# Power.net
KiCad netlist of a schematic drawn in Altium Designer
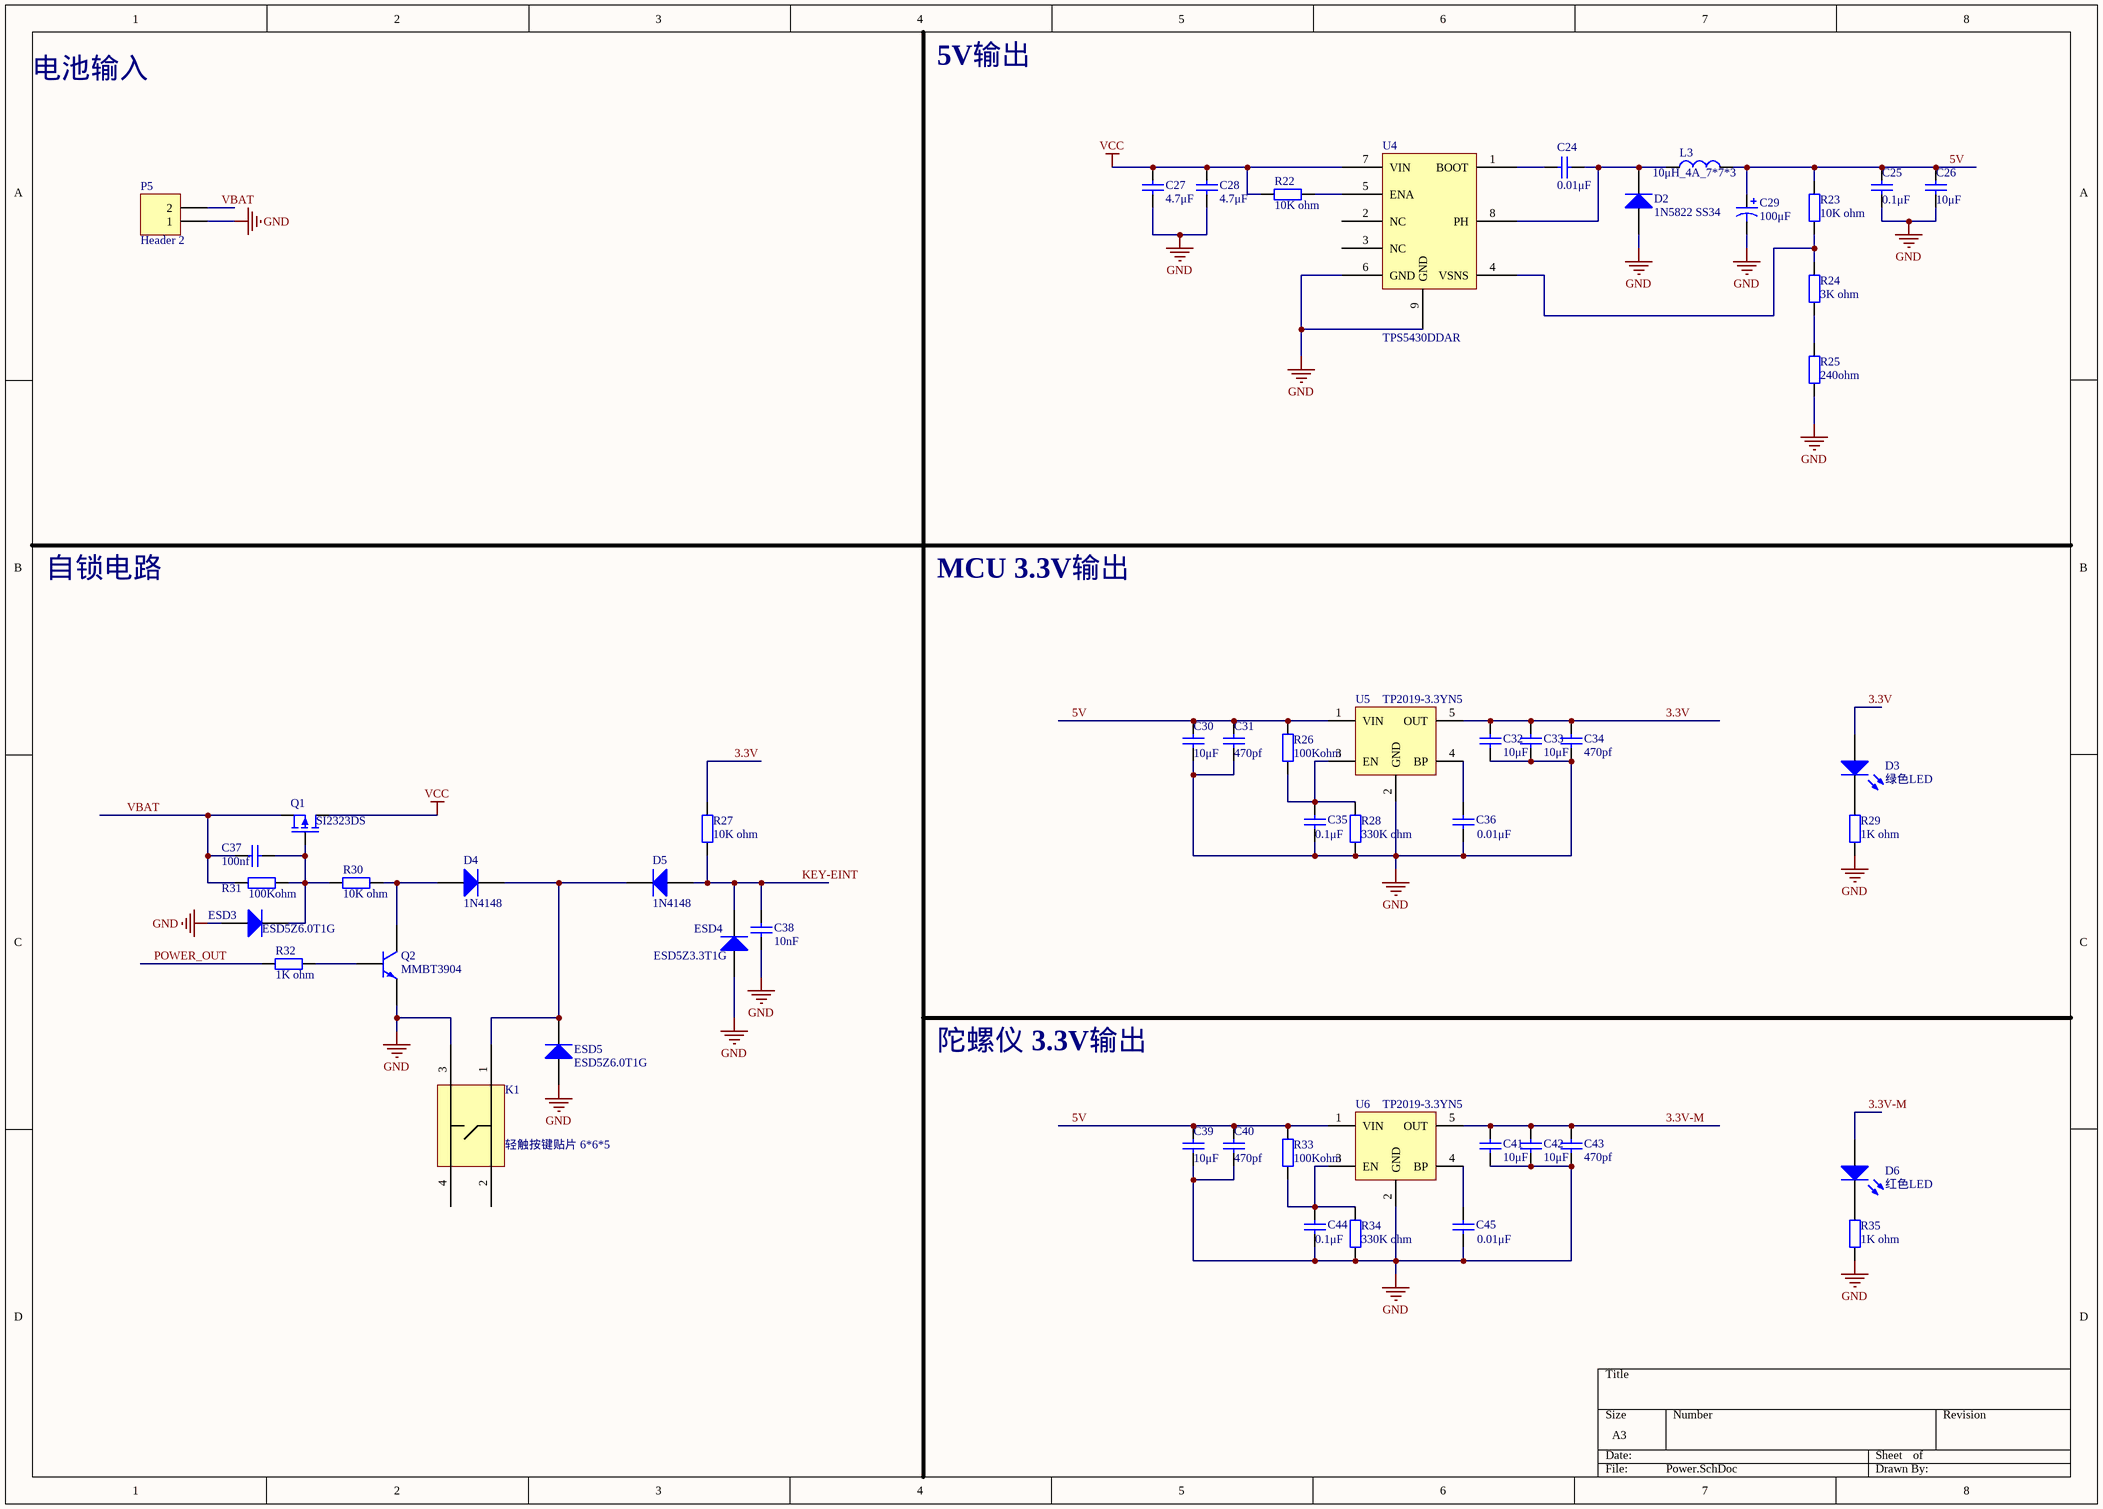
[diagram p0: Power.SchDoc]

(export (version "E")
  (design (tool "Eeschema 10.0.6"))
  (components
    (comp (ref "C24")
      (value "0.01μF")
      (footprint "0603C")
      (description "0.01μF_50V,C0G,5%")
      (libsource (lib "Yang_Lib") (part "Cap_0.01μF_50V_0603"))
    )
    (comp (ref "C25")
      (value "0.1μF")
      (footprint "0603C")
      (description "0.1μF_50V,X7R,±5%")
      (libsource (lib "Yang_Lib") (part "Cap_0.1μF_50V_0603"))
    )
    (comp (ref "C26")
      (value "10μF")
      (footprint "1206C")
      (description "10μF_10V,10%")
      (libsource (lib "Yang_Lib") (part "Cap_10μF_10V_1206"))
    )
    (comp (ref "C27")
      (value "4.7μF")
      (footprint "1206C")
      (description "4.7μF_35VJB,±10%")
      (libsource (lib "Yang_Lib") (part "Cap_4.7μF_35V_1206"))
    )
    (comp (ref "C28")
      (value "4.7μF")
      (footprint "1206C")
      (description "4.7μF_35VJB,±10%")
      (libsource (lib "Yang_Lib") (part "Cap_4.7μF_35V_1206"))
    )
    (comp (ref "C29")
      (value "100μF")
      (footprint "D7343C")
      (description "100μF_16V")
      (libsource (lib "Yang_Lib") (part "Cap_100μF_16V_D7343"))
    )
    (comp (ref "C30")
      (value "10μF")
      (footprint "0603C")
      (description "10μF_35V,X5R,20%")
      (libsource (lib "Yang_Lib") (part "Cap_10μF_35V_0603"))
    )
    (comp (ref "C31")
      (value "470pf")
      (footprint "0603C")
      (description "470pf_50V,X7R,10%")
      (libsource (lib "Yang_Lib") (part "Cap_470pf_50V_0603"))
    )
    (comp (ref "C32")
      (value "10μF")
      (footprint "0603C")
      (description "10μF_35V,X5R,20%")
      (libsource (lib "Yang_Lib") (part "Cap_10μF_35V_0603"))
    )
    (comp (ref "C33")
      (value "10μF")
      (footprint "0603C")
      (description "10μF_35V,X5R,20%")
      (libsource (lib "Yang_Lib") (part "Cap_10μF_35V_0603"))
    )
    (comp (ref "C34")
      (value "470pf")
      (footprint "0603C")
      (description "470pf_50V,X7R,10%")
      (libsource (lib "Yang_Lib") (part "Cap_470pf_50V_0603"))
    )
    (comp (ref "C35")
      (value "0.1μF")
      (footprint "0603C")
      (description "0.1μF_50V,X7R,±5%")
      (libsource (lib "Yang_Lib") (part "Cap_0.1μF_50V_0603"))
    )
    (comp (ref "C36")
      (value "0.01μF")
      (footprint "0603C")
      (description "0.01μF_50V,C0G,5%")
      (libsource (lib "Yang_Lib") (part "Cap_0.01μF_50V_0603"))
    )
    (comp (ref "C37")
      (value "100nf")
      (footprint "0603C")
      (description "100nf_50V,X5R,10%")
      (libsource (lib "Yang_Lib") (part "Cap_100nf_50V_0603"))
    )
    (comp (ref "C38")
      (value "10nF")
      (footprint "0603C")
      (description "10nF/16V,0603")
      (libsource (lib "Yang_Lib") (part "Cap_10nF_16V_0603"))
    )
    (comp (ref "C39")
      (value "10μF")
      (footprint "0603C")
      (description "10μF_35V,X5R,20%")
      (libsource (lib "Yang_Lib") (part "Cap_10μF_35V_0603"))
    )
    (comp (ref "C40")
      (value "470pf")
      (footprint "0603C")
      (description "470pf_50V,X7R,10%")
      (libsource (lib "Yang_Lib") (part "Cap_470pf_50V_0603"))
    )
    (comp (ref "C41")
      (value "10μF")
      (footprint "0603C")
      (description "10μF_35V,X5R,20%")
      (libsource (lib "Yang_Lib") (part "Cap_10μF_35V_0603"))
    )
    (comp (ref "C42")
      (value "10μF")
      (footprint "0603C")
      (description "10μF_35V,X5R,20%")
      (libsource (lib "Yang_Lib") (part "Cap_10μF_35V_0603"))
    )
    (comp (ref "C43")
      (value "470pf")
      (footprint "0603C")
      (description "470pf_50V,X7R,10%")
      (libsource (lib "Yang_Lib") (part "Cap_470pf_50V_0603"))
    )
    (comp (ref "C44")
      (value "0.1μF")
      (footprint "0603C")
      (description "0.1μF_50V,X7R,±5%")
      (libsource (lib "Yang_Lib") (part "Cap_0.1μF_50V_0603"))
    )
    (comp (ref "C45")
      (value "0.01μF")
      (footprint "0603C")
      (description "0.01μF_50V,C0G,5%")
      (libsource (lib "Yang_Lib") (part "Cap_0.01μF_50V_0603"))
    )
    (comp (ref "D2")
      (value "1N5822 SS34")
      (footprint "SMA-small")
      (libsource (lib "Yang_Lib") (part "1N5822 SS34_SMA"))
    )
    (comp (ref "D3")
      (value "绿色LED")
      (footprint "Yang_Lib:0603LED")
      (description "蓝色LED")
      (libsource (lib "FSR_BodyLib") (part "蓝色LED"))
    )
    (comp (ref "D4")
      (value "1N4148")
      (footprint "SOD323")
      (description "1N4148WS")
      (libsource (lib "Yang_Lib") (part "1N4148WS_SOD323"))
    )
    (comp (ref "D5")
      (value "1N4148")
      (footprint "SOD323")
      (description "1N4148WS")
      (libsource (lib "Yang_Lib") (part "1N4148WS_SOD323"))
    )
    (comp (ref "D6")
      (value "红色LED")
      (footprint "Yang_Lib:0603LED")
      (description "蓝色LED")
      (libsource (lib "FSR_BodyLib") (part "蓝色LED"))
    )
    (comp (ref "ESD3")
      (value "ESD5Z6.0T1G")
      (footprint "SOD523")
      (libsource (lib "Yang_Lib") (part "ESD5Z6.0T1G_SOD523"))
    )
    (comp (ref "ESD4")
      (value "ESD5Z3.3T1G")
      (footprint "SOD523")
      (libsource (lib "Yang_Lib") (part "ESD5Z3.3T1G_SOD523"))
    )
    (comp (ref "ESD5")
      (value "ESD5Z6.0T1G")
      (footprint "SOD523")
      (libsource (lib "Yang_Lib") (part "ESD5Z6.0T1G_SOD523"))
    )
    (comp (ref "K1")
      (value "轻触按键贴片 6*6*5")
      (footprint "轻触按键贴片 6*6*5")
      (libsource (lib "Yang_Lib") (part "轻触按键贴片 6*6*5"))
    )
    (comp (ref "L3")
      (value "10μH_4A_7*7*3")
      (footprint "7*7*3mm - 06030")
      (description "10μH_4A")
      (libsource (lib "Yang_Lib") (part "10μH_4A_7*7*3"))
    )
    (comp (ref "P5")
      (value "Header 2")
      (footprint "HDR1X2")
      (description "Header, 2-Pin")
      (fields (field (name "PUBLISHER") "Altium Limited"))
      (libsource (lib "Miscellaneous Connectors") (part "Header 2"))
    )
    (comp (ref "Q1") (value "SI2323DS") (footprint "SOT-23") (libsource (lib "Yang_Lib") (part "SI2323DS")))
    (comp (ref "Q2") (value "MMBT3904") (footprint "SOT-23") (libsource (lib "Yang_Lib") (part "MMBT3904")))
    (comp (ref "R22")
      (value "10K ohm")
      (footprint "0603R")
      (description "10K ohm,1%")
      (libsource (lib "") (part "Res_10K ohm_0603_1"))
    )
    (comp (ref "R23")
      (value "10K ohm")
      (footprint "0603R")
      (description "10K ohm,1%")
      (libsource (lib "Yang_Lib") (part "Res_10K ohm_0603"))
    )
    (comp (ref "R24")
      (value "3K ohm")
      (footprint "0603R")
      (description "3K ohm,1%")
      (libsource (lib "Yang_Lib") (part "Res_3K ohm_0603"))
    )
    (comp (ref "R25")
      (value "240ohm")
      (footprint "0603R")
      (description "240ohm,1%")
      (libsource (lib "Yang_Lib") (part "Res_240ohm_0603"))
    )
    (comp (ref "R26")
      (value "100Kohm")
      (footprint "0603R")
      (description "100K ohm_1%")
      (libsource (lib "Yang_Lib") (part "Res_100Kohm_0603"))
    )
    (comp (ref "R27")
      (value "10K ohm")
      (footprint "0603R")
      (description "10K ohm,1%")
      (libsource (lib "Yang_Lib") (part "Res_10K ohm_0603"))
    )
    (comp (ref "R28")
      (value "330K ohm")
      (footprint "0603R")
      (description "330K ohm,1%")
      (libsource (lib "Yang_Lib") (part "Res_330K ohm_0603"))
    )
    (comp (ref "R29")
      (value "1K ohm")
      (footprint "0603R")
      (description "1K ohm,1%")
      (libsource (lib "Yang_Lib") (part "Res_1K ohm_0603"))
    )
    (comp (ref "R30")
      (value "10K ohm")
      (footprint "0603R")
      (description "10K ohm,1%")
      (libsource (lib "") (part "Res_10K ohm_0603_1"))
    )
    (comp (ref "R31")
      (value "100Kohm")
      (footprint "0603R")
      (description "100K ohm_5%")
      (libsource (lib "") (part "Res_100Kohm_0603_1"))
    )
    (comp (ref "R32")
      (value "1K ohm")
      (footprint "0603R")
      (description "1K ohm,1%")
      (libsource (lib "") (part "Res_1K ohm_0603_1"))
    )
    (comp (ref "R33")
      (value "100Kohm")
      (footprint "0603R")
      (description "100K ohm_1%")
      (libsource (lib "Yang_Lib") (part "Res_100Kohm_0603"))
    )
    (comp (ref "R34")
      (value "330K ohm")
      (footprint "0603R")
      (description "330K ohm,1%")
      (libsource (lib "Yang_Lib") (part "Res_330K ohm_0603"))
    )
    (comp (ref "R35")
      (value "1K ohm")
      (footprint "0603R")
      (description "1K ohm,1%")
      (libsource (lib "Yang_Lib") (part "Res_1K ohm_0603"))
    )
    (comp (ref "U4")
      (value "TPS5430DDAR")
      (footprint "SOIC8-PAD")
      (libsource (lib "Yang_Lib") (part "TPS5430DDAR"))
    )
    (comp (ref "U5")
      (value "TP2019-3.3YN5")
      (footprint "SOT-23-5")
      (libsource (lib "Yang_Lib") (part "TP2019-3.3YN5"))
    )
    (comp (ref "U6")
      (value "TP2019-3.3YN5")
      (footprint "SOT-23-5")
      (libsource (lib "Yang_Lib") (part "TP2019-3.3YN5"))
    )
  )
  (nets
    (net (code "1") (name "/3.3V") (class "Default")
      (node (ref "C32") (pin "2") (pinfunction "2_2") (pintype "passive"))
      (node (ref "C33") (pin "2") (pinfunction "2_2") (pintype "passive"))
      (node (ref "C34") (pin "2") (pinfunction "2_2") (pintype "passive"))
      (node (ref "D3") (pin "1") (pinfunction "A_1") (pintype "passive"))
      (node (ref "R27") (pin "2") (pinfunction "2_2") (pintype "passive"))
      (node (ref "U5") (pin "5") (pinfunction "OUT_5") (pintype "passive"))
    )
    (net (code "2") (name "/3.3V-M") (class "Default")
      (node (ref "C41") (pin "2") (pinfunction "2_2") (pintype "passive"))
      (node (ref "C42") (pin "2") (pinfunction "2_2") (pintype "passive"))
      (node (ref "C43") (pin "2") (pinfunction "2_2") (pintype "passive"))
      (node (ref "D6") (pin "1") (pinfunction "A_1") (pintype "passive"))
      (node (ref "U6") (pin "5") (pinfunction "OUT_5") (pintype "passive"))
    )
    (net (code "3") (name "/5V") (class "Default")
      (node (ref "C25") (pin "2") (pinfunction "2_2") (pintype "passive"))
      (node (ref "C26") (pin "2") (pinfunction "2_2") (pintype "passive"))
      (node (ref "C29") (pin "1") (pinfunction "1_1") (pintype "passive"))
      (node (ref "C30") (pin "2") (pinfunction "2_2") (pintype "passive"))
      (node (ref "C31") (pin "2") (pinfunction "2_2") (pintype "passive"))
      (node (ref "C39") (pin "2") (pinfunction "2_2") (pintype "passive"))
      (node (ref "C40") (pin "2") (pinfunction "2_2") (pintype "passive"))
      (node (ref "L3") (pin "2") (pinfunction "2_2") (pintype "passive"))
      (node (ref "R23") (pin "2") (pinfunction "2_2") (pintype "passive"))
      (node (ref "R26") (pin "2") (pinfunction "2_2") (pintype "passive"))
      (node (ref "R33") (pin "2") (pinfunction "2_2") (pintype "passive"))
      (node (ref "U5") (pin "1") (pinfunction "VIN_1") (pintype "passive"))
      (node (ref "U6") (pin "1") (pinfunction "VIN_1") (pintype "passive"))
    )
    (net (code "4") (name "/KEY-EINT") (class "Default")
      (node (ref "C38") (pin "2") (pinfunction "2_2") (pintype "passive"))
      (node (ref "D5") (pin "1") (pinfunction "A_1") (pintype "passive"))
      (node (ref "ESD4") (pin "2") (pinfunction "K_2") (pintype "passive"))
      (node (ref "R27") (pin "1") (pinfunction "1_1") (pintype "passive"))
    )
    (net (code "5") (name "/POWER_OUT") (class "Default")
      (node (ref "R32") (pin "1") (pinfunction "1_1") (pintype "passive"))
    )
    (net (code "6") (name "/VBAT") (class "Default")
      (node (ref "C37") (pin "1") (pinfunction "1_1") (pintype "passive"))
      (node (ref "P5") (pin "2") (pinfunction "2_2") (pintype "passive"))
      (node (ref "Q1") (pin "3") (pinfunction "S_3") (pintype "passive"))
      (node (ref "R31") (pin "1") (pinfunction "1_1") (pintype "passive"))
    )
    (net (code "7") (name "GND") (class "Default")
      (node (ref "C25") (pin "1") (pinfunction "1_1") (pintype "passive"))
      (node (ref "C26") (pin "1") (pinfunction "1_1") (pintype "passive"))
      (node (ref "C27") (pin "2") (pinfunction "2_2") (pintype "passive"))
      (node (ref "C28") (pin "1") (pinfunction "1_1") (pintype "passive"))
      (node (ref "C29") (pin "2") (pinfunction "2_2") (pintype "passive"))
      (node (ref "C30") (pin "1") (pinfunction "1_1") (pintype "passive"))
      (node (ref "C31") (pin "1") (pinfunction "1_1") (pintype "passive"))
      (node (ref "C32") (pin "1") (pinfunction "1_1") (pintype "passive"))
      (node (ref "C33") (pin "1") (pinfunction "1_1") (pintype "passive"))
      (node (ref "C34") (pin "1") (pinfunction "1_1") (pintype "passive"))
      (node (ref "C35") (pin "1") (pinfunction "1_1") (pintype "passive"))
      (node (ref "C36") (pin "1") (pinfunction "1_1") (pintype "passive"))
      (node (ref "C38") (pin "1") (pinfunction "1_1") (pintype "passive"))
      (node (ref "C39") (pin "1") (pinfunction "1_1") (pintype "passive"))
      (node (ref "C40") (pin "1") (pinfunction "1_1") (pintype "passive"))
      (node (ref "C41") (pin "1") (pinfunction "1_1") (pintype "passive"))
      (node (ref "C42") (pin "1") (pinfunction "1_1") (pintype "passive"))
      (node (ref "C43") (pin "1") (pinfunction "1_1") (pintype "passive"))
      (node (ref "C44") (pin "1") (pinfunction "1_1") (pintype "passive"))
      (node (ref "C45") (pin "1") (pinfunction "1_1") (pintype "passive"))
      (node (ref "D2") (pin "1") (pinfunction "A_1") (pintype "passive"))
      (node (ref "ESD3") (pin "1") (pinfunction "A_1") (pintype "passive"))
      (node (ref "ESD4") (pin "1") (pinfunction "A_1") (pintype "passive"))
      (node (ref "ESD5") (pin "1") (pinfunction "A_1") (pintype "passive"))
      (node (ref "K1") (pin "3") (pinfunction "3_3") (pintype "passive"))
      (node (ref "P5") (pin "1") (pinfunction "1_1") (pintype "passive"))
      (node (ref "Q2") (pin "3") (pinfunction "E_3") (pintype "passive"))
      (node (ref "R25") (pin "1") (pinfunction "1_1") (pintype "passive"))
      (node (ref "R28") (pin "1") (pinfunction "1_1") (pintype "passive"))
      (node (ref "R29") (pin "1") (pinfunction "1_1") (pintype "passive"))
      (node (ref "R34") (pin "1") (pinfunction "1_1") (pintype "passive"))
      (node (ref "R35") (pin "1") (pinfunction "1_1") (pintype "passive"))
      (node (ref "U4") (pin "6") (pinfunction "GND_6") (pintype "passive"))
      (node (ref "U4") (pin "9") (pinfunction "GND_9") (pintype "passive"))
      (node (ref "U5") (pin "2") (pinfunction "GND_2") (pintype "passive"))
      (node (ref "U6") (pin "2") (pinfunction "GND_2") (pintype "passive"))
    )
    (net (code "8") (name "Net-(D2-K)") (class "Default")
      (node (ref "C24") (pin "2") (pinfunction "2_2") (pintype "passive"))
      (node (ref "D2") (pin "2") (pinfunction "K_2") (pintype "passive"))
      (node (ref "L3") (pin "1") (pinfunction "1_1") (pintype "passive"))
      (node (ref "U4") (pin "8") (pinfunction "PH_8") (pintype "passive"))
    )
    (net (code "9") (name "Net-(D3-K)") (class "Default")
      (node (ref "D3") (pin "2") (pinfunction "K_2") (pintype "passive"))
      (node (ref "R29") (pin "2") (pinfunction "2_2") (pintype "passive"))
    )
    (net (code "10") (name "Net-(D4-A)") (class "Default")
      (node (ref "D4") (pin "1") (pinfunction "A_1") (pintype "passive"))
      (node (ref "Q2") (pin "2") (pinfunction "C_2") (pintype "passive"))
      (node (ref "R30") (pin "2") (pinfunction "2_2") (pintype "passive"))
    )
    (net (code "11") (name "Net-(D4-K)") (class "Default")
      (node (ref "D4") (pin "2") (pinfunction "K_2") (pintype "passive"))
      (node (ref "D5") (pin "2") (pinfunction "K_2") (pintype "passive"))
      (node (ref "ESD5") (pin "2") (pinfunction "K_2") (pintype "passive"))
      (node (ref "K1") (pin "1") (pinfunction "1_1") (pintype "passive"))
    )
    (net (code "12") (name "Net-(D6-K)") (class "Default")
      (node (ref "D6") (pin "2") (pinfunction "K_2") (pintype "passive"))
      (node (ref "R35") (pin "2") (pinfunction "2_2") (pintype "passive"))
    )
    (net (code "13") (name "Net-(ESD3-K)") (class "Default")
      (node (ref "C37") (pin "2") (pinfunction "2_2") (pintype "passive"))
      (node (ref "ESD3") (pin "2") (pinfunction "K_2") (pintype "passive"))
      (node (ref "Q1") (pin "1") (pinfunction "G_1") (pintype "passive"))
      (node (ref "R30") (pin "1") (pinfunction "1_1") (pintype "passive"))
      (node (ref "R31") (pin "2") (pinfunction "2_2") (pintype "passive"))
    )
    (net (code "14") (name "Net-(Q2-B)") (class "Default")
      (node (ref "Q2") (pin "1") (pinfunction "B_1") (pintype "passive"))
      (node (ref "R32") (pin "2") (pinfunction "2_2") (pintype "passive"))
    )
    (net (code "15") (name "Net-(R24-Pad1)") (class "Default")
      (node (ref "R24") (pin "1") (pinfunction "1_1") (pintype "passive"))
      (node (ref "R25") (pin "2") (pinfunction "2_2") (pintype "passive"))
    )
    (net (code "16") (name "Net-(U4-BOOT)") (class "Default")
      (node (ref "C24") (pin "1") (pinfunction "1_1") (pintype "passive"))
      (node (ref "U4") (pin "1") (pinfunction "BOOT_1") (pintype "passive"))
    )
    (net (code "17") (name "Net-(U4-ENA)") (class "Default")
      (node (ref "R22") (pin "2") (pinfunction "2_2") (pintype "passive"))
      (node (ref "U4") (pin "5") (pinfunction "ENA_5") (pintype "passive"))
    )
    (net (code "18") (name "Net-(U4-VSNS)") (class "Default")
      (node (ref "R23") (pin "1") (pinfunction "1_1") (pintype "passive"))
      (node (ref "R24") (pin "2") (pinfunction "2_2") (pintype "passive"))
      (node (ref "U4") (pin "4") (pinfunction "VSNS_4") (pintype "passive"))
    )
    (net (code "19") (name "Net-(U5-BP)") (class "Default")
      (node (ref "C36") (pin "2") (pinfunction "2_2") (pintype "passive"))
      (node (ref "U5") (pin "4") (pinfunction "BP_4") (pintype "passive"))
    )
    (net (code "20") (name "Net-(U5-EN)") (class "Default")
      (node (ref "C35") (pin "2") (pinfunction "2_2") (pintype "passive"))
      (node (ref "R26") (pin "1") (pinfunction "1_1") (pintype "passive"))
      (node (ref "R28") (pin "2") (pinfunction "2_2") (pintype "passive"))
      (node (ref "U5") (pin "3") (pinfunction "EN_3") (pintype "passive"))
    )
    (net (code "21") (name "Net-(U6-BP)") (class "Default")
      (node (ref "C45") (pin "2") (pinfunction "2_2") (pintype "passive"))
      (node (ref "U6") (pin "4") (pinfunction "BP_4") (pintype "passive"))
    )
    (net (code "22") (name "Net-(U6-EN)") (class "Default")
      (node (ref "C44") (pin "2") (pinfunction "2_2") (pintype "passive"))
      (node (ref "R33") (pin "1") (pinfunction "1_1") (pintype "passive"))
      (node (ref "R34") (pin "2") (pinfunction "2_2") (pintype "passive"))
      (node (ref "U6") (pin "3") (pinfunction "EN_3") (pintype "passive"))
    )
    (net (code "23") (name "VCC") (class "Default")
      (node (ref "C27") (pin "1") (pinfunction "1_1") (pintype "passive"))
      (node (ref "C28") (pin "2") (pinfunction "2_2") (pintype "passive"))
      (node (ref "Q1") (pin "2") (pinfunction "D_2") (pintype "passive"))
      (node (ref "R22") (pin "1") (pinfunction "1_1") (pintype "passive"))
      (node (ref "U4") (pin "7") (pinfunction "VIN_7") (pintype "passive"))
    )
    (net (code "24") (name "unconnected-(K1-Pad2)") (class "Default")
      (node (ref "K1") (pin "2") (pinfunction "2_2") (pintype "passive"))
    )
    (net (code "25") (name "unconnected-(K1-Pad4)") (class "Default")
      (node (ref "K1") (pin "4") (pinfunction "4_4") (pintype "passive"))
    )
    (net (code "26") (name "unconnected-(U4-NC-Pad2)") (class "Default")
      (node (ref "U4") (pin "2") (pinfunction "NC_2") (pintype "passive"))
    )
    (net (code "27") (name "unconnected-(U4-NC-Pad3)") (class "Default")
      (node (ref "U4") (pin "3") (pinfunction "NC_3") (pintype "passive"))
    )
  )
)
